# Swarm_Board.net
KiCad netlist of a schematic drawn in EAGLE
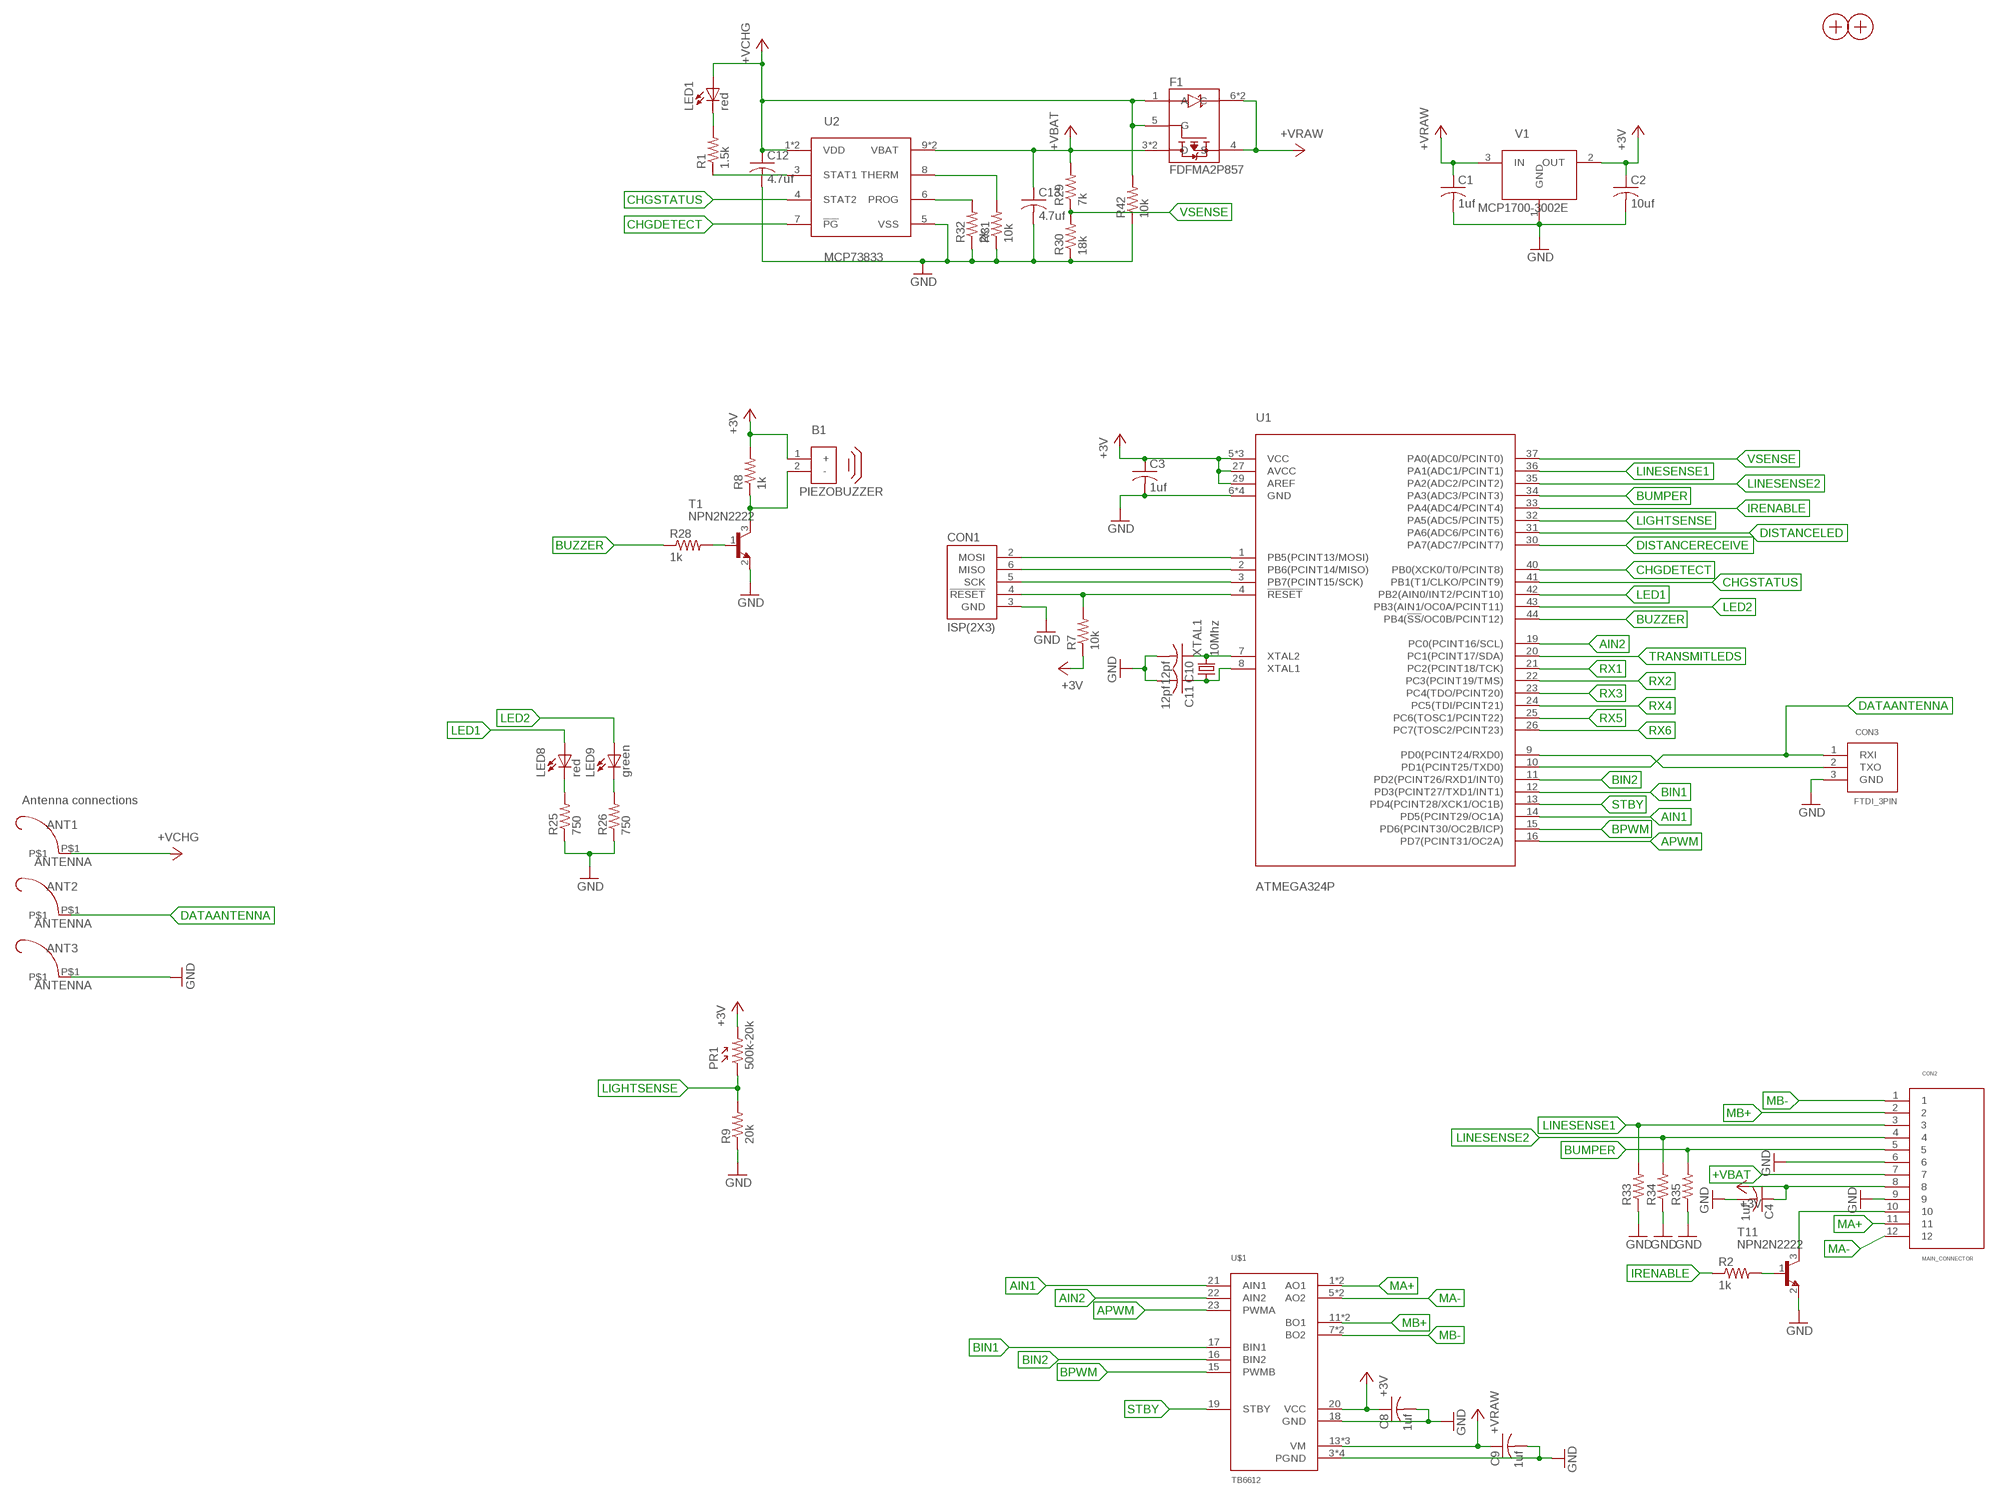
[diagram p0: schematic, sheet 1, part 1 of 2]
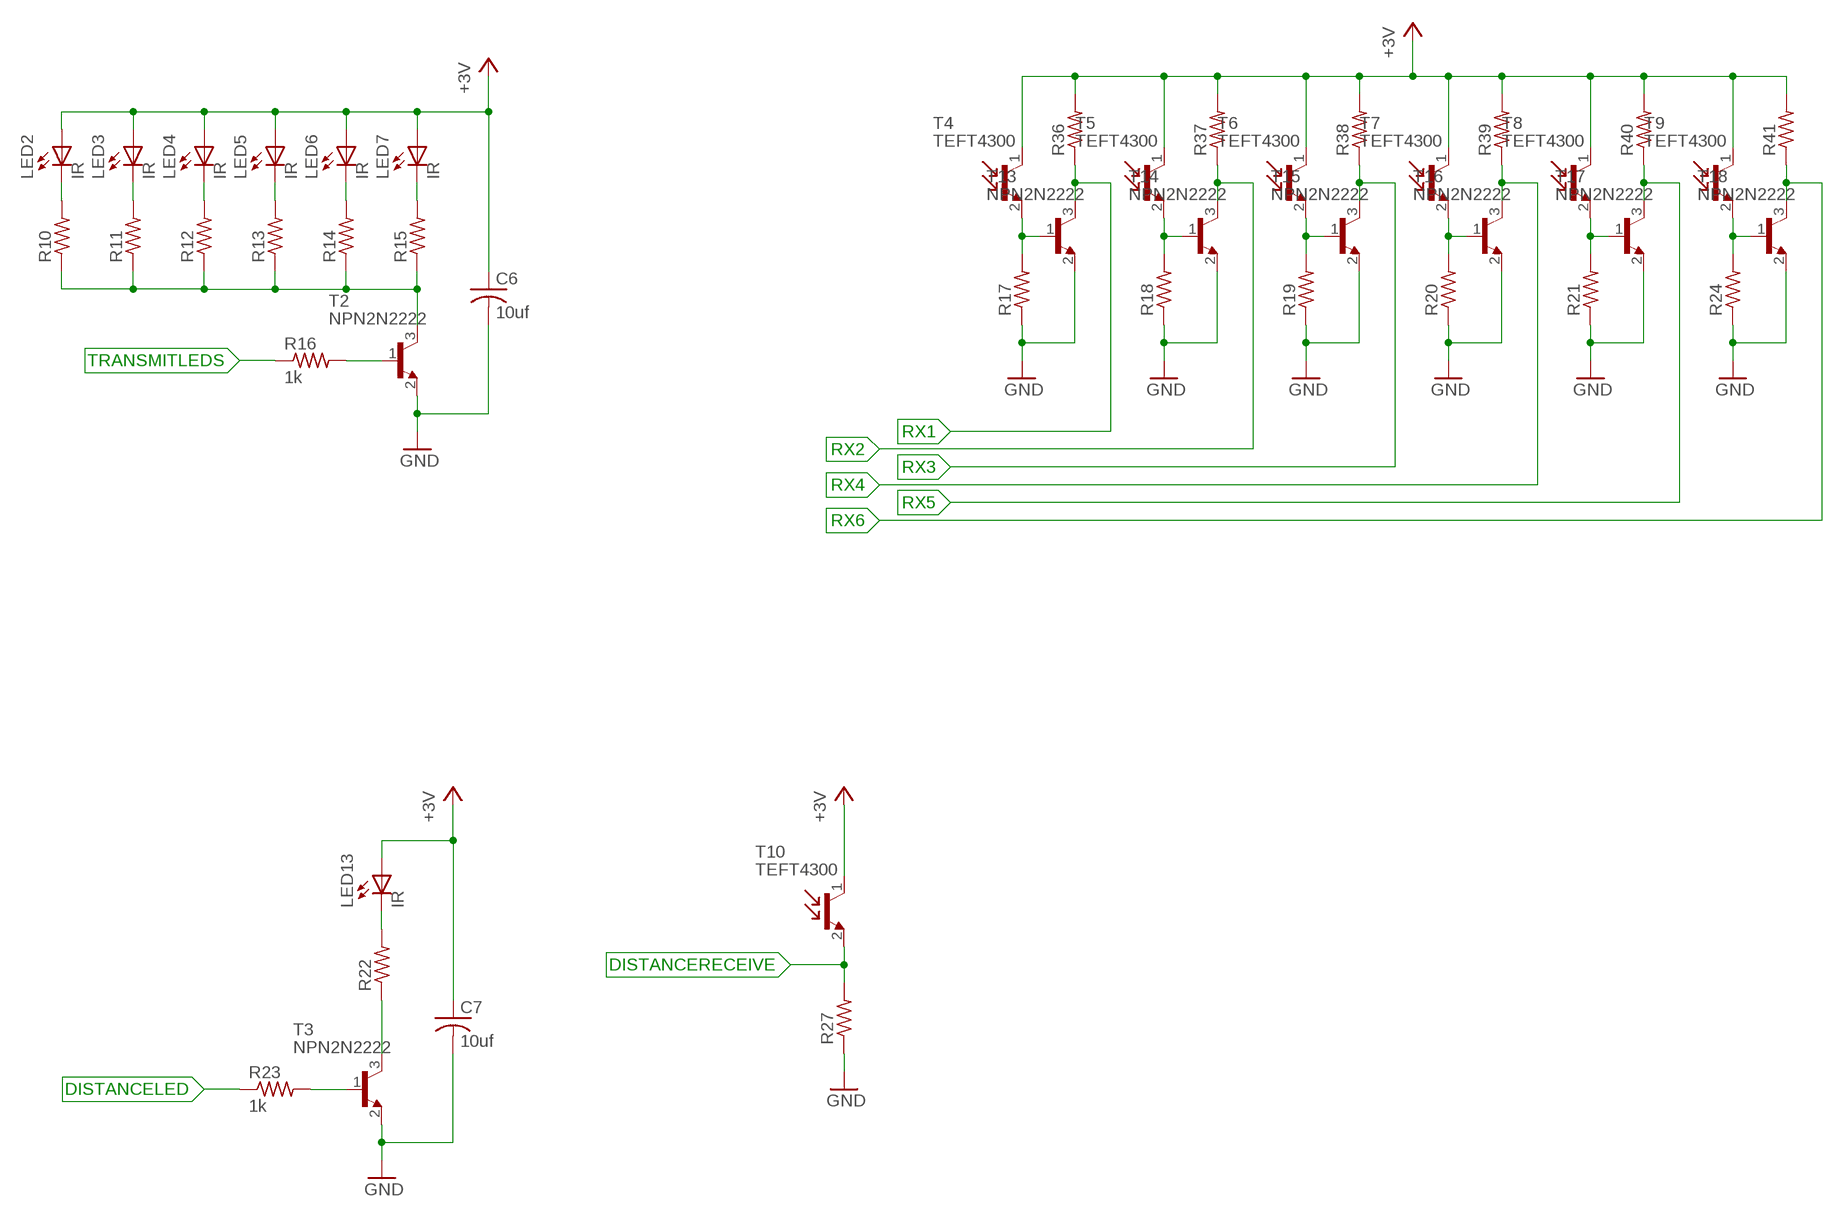
[diagram p1: schematic, sheet 1, part 2 of 2]

(export (version "E")
  (design (tool "Eeschema 10.0.6"))
  (components
    (comp (ref "ANT1")
      (value "ANTENNA")
      (footprint "eagle-import:ANTENNA")
      (libsource (lib "eagle-import") (part "ANTENNA"))
    )
    (comp (ref "ANT2")
      (value "ANTENNA")
      (footprint "eagle-import:ANTENNA")
      (libsource (lib "eagle-import") (part "ANTENNA"))
    )
    (comp (ref "ANT3")
      (value "ANTENNA")
      (footprint "eagle-import:ANTENNA")
      (libsource (lib "eagle-import") (part "ANTENNA"))
    )
    (comp (ref "B1")
      (value "PIEZOBUZZER")
      (footprint "eagle-import:PIEZOBUZZER")
      (libsource (lib "eagle-import") (part "PIEZOBUZZER"))
    )
    (comp (ref "C1")
      (value "1uf")
      (footprint "eagle-import:0603")
      (libsource (lib "eagle-import") (part "CAP0603"))
    )
    (comp (ref "C2")
      (value "10uf")
      (footprint "eagle-import:0805")
      (libsource (lib "eagle-import") (part "CAP0805"))
    )
    (comp (ref "C3")
      (value "1uf")
      (footprint "eagle-import:0603")
      (libsource (lib "eagle-import") (part "CAP0603"))
    )
    (comp (ref "C4")
      (value "1uf")
      (footprint "eagle-import:0603")
      (libsource (lib "eagle-import") (part "CAP0603"))
    )
    (comp (ref "C6")
      (value "10uf")
      (footprint "eagle-import:0805")
      (libsource (lib "eagle-import") (part "CAP0805"))
    )
    (comp (ref "C7")
      (value "10uf")
      (footprint "eagle-import:0805")
      (libsource (lib "eagle-import") (part "CAP0805"))
    )
    (comp (ref "C8")
      (value "1uf")
      (footprint "eagle-import:0603")
      (libsource (lib "eagle-import") (part "CAP0603"))
    )
    (comp (ref "C9")
      (value "1uf")
      (footprint "eagle-import:0603")
      (libsource (lib "eagle-import") (part "CAP0603"))
    )
    (comp (ref "C10")
      (value "12pf")
      (footprint "eagle-import:0603")
      (libsource (lib "eagle-import") (part "CAP0603"))
    )
    (comp (ref "C11")
      (value "12pf")
      (footprint "eagle-import:0603")
      (libsource (lib "eagle-import") (part "CAP0603"))
    )
    (comp (ref "C12")
      (value "4.7uf")
      (footprint "eagle-import:0603")
      (libsource (lib "eagle-import") (part "CAP0603"))
    )
    (comp (ref "C13")
      (value "4.7uf")
      (footprint "eagle-import:0603")
      (libsource (lib "eagle-import") (part "CAP0603"))
    )
    (comp (ref "CON1")
      (value "ISP(2X3)")
      (footprint "eagle-import:PINHEADER(2X3)")
      (libsource (lib "eagle-import") (part "ISP(2X3)"))
    )
    (comp (ref "CON2")
      (value "MAIN_CONNECTOR")
      (footprint "eagle-import:FEMALE_HEADER_2MM_2X6")
      (libsource (lib "eagle-import") (part "MAIN_CONNECTOR"))
    )
    (comp (ref "CON3")
      (value "FTDI_3PIN")
      (footprint "eagle-import:3PINHEADER_.100_")
      (libsource (lib "eagle-import") (part "FTDI_3PIN"))
    )
    (comp (ref "F1")
      (value "FDFMA2P857")
      (footprint "eagle-import:MICROFET2X2MM")
      (libsource (lib "eagle-import") (part "FDFMA2P857"))
    )
    (comp (ref "H1")
      (value "MOUNTINGHOLE")
      (footprint "eagle-import:MOUNTINGHOLE")
      (libsource (lib "eagle-import") (part "MOUNTINGHOLE"))
    )
    (comp (ref "H2")
      (value "MOUNTINGHOLE")
      (footprint "eagle-import:MOUNTINGHOLE")
      (libsource (lib "eagle-import") (part "MOUNTINGHOLE"))
    )
    (comp (ref "LED1")
      (value "red")
      (footprint "eagle-import:LED0603")
      (libsource (lib "eagle-import") (part "LED0603"))
    )
    (comp (ref "LED2")
      (value "IR")
      (footprint "eagle-import:5MM_LED_RA")
      (libsource (lib "eagle-import") (part "LED5MMRA"))
    )
    (comp (ref "LED3")
      (value "IR")
      (footprint "eagle-import:5MM_LED_RA")
      (libsource (lib "eagle-import") (part "LED5MMRA"))
    )
    (comp (ref "LED4")
      (value "IR")
      (footprint "eagle-import:5MM_LED_RA")
      (libsource (lib "eagle-import") (part "LED5MMRA"))
    )
    (comp (ref "LED5")
      (value "IR")
      (footprint "eagle-import:5MM_LED_RA")
      (libsource (lib "eagle-import") (part "LED5MMRA"))
    )
    (comp (ref "LED6")
      (value "IR")
      (footprint "eagle-import:5MM_LED_RA")
      (libsource (lib "eagle-import") (part "LED5MMRA"))
    )
    (comp (ref "LED7")
      (value "IR")
      (footprint "eagle-import:5MM_LED_RA")
      (libsource (lib "eagle-import") (part "LED5MMRA"))
    )
    (comp (ref "LED8")
      (value "red")
      (footprint "eagle-import:LED0603")
      (libsource (lib "eagle-import") (part "LED0603"))
    )
    (comp (ref "LED9")
      (value "green")
      (footprint "eagle-import:LED0603")
      (libsource (lib "eagle-import") (part "LED0603"))
    )
    (comp (ref "LED13")
      (value "IR")
      (footprint "eagle-import:5MM_LED_RA")
      (libsource (lib "eagle-import") (part "LED5MMRA"))
    )
    (comp (ref "PR1")
      (value "500k-20k")
      (footprint "eagle-import:CDSPHOTOCELL")
      (libsource (lib "eagle-import") (part "CDSPHOTORESISTOR"))
    )
    (comp (ref "R1")
      (value "1.5k")
      (footprint "eagle-import:0603")
      (libsource (lib "eagle-import") (part "RES0603"))
    )
    (comp (ref "R2")
      (value "1k")
      (footprint "eagle-import:0603")
      (libsource (lib "eagle-import") (part "RES0603"))
    )
    (comp (ref "R7")
      (value "10k")
      (footprint "eagle-import:0603")
      (libsource (lib "eagle-import") (part "RES0603"))
    )
    (comp (ref "R8")
      (value "1k")
      (footprint "eagle-import:0603")
      (libsource (lib "eagle-import") (part "RES0603"))
    )
    (comp (ref "R9")
      (value "20k")
      (footprint "eagle-import:0603")
      (libsource (lib "eagle-import") (part "RES0603"))
    )
    (comp (ref "R10")
      (value "RES0603")
      (footprint "eagle-import:0603")
      (libsource (lib "eagle-import") (part "RES0603"))
    )
    (comp (ref "R11")
      (value "RES0603")
      (footprint "eagle-import:0603")
      (libsource (lib "eagle-import") (part "RES0603"))
    )
    (comp (ref "R12")
      (value "RES0603")
      (footprint "eagle-import:0603")
      (libsource (lib "eagle-import") (part "RES0603"))
    )
    (comp (ref "R13")
      (value "RES0603")
      (footprint "eagle-import:0603")
      (libsource (lib "eagle-import") (part "RES0603"))
    )
    (comp (ref "R14")
      (value "RES0603")
      (footprint "eagle-import:0603")
      (libsource (lib "eagle-import") (part "RES0603"))
    )
    (comp (ref "R15")
      (value "RES0603")
      (footprint "eagle-import:0603")
      (libsource (lib "eagle-import") (part "RES0603"))
    )
    (comp (ref "R16")
      (value "1k")
      (footprint "eagle-import:0603")
      (libsource (lib "eagle-import") (part "RES0603"))
    )
    (comp (ref "R17")
      (value "RES0603")
      (footprint "eagle-import:0603")
      (libsource (lib "eagle-import") (part "RES0603"))
    )
    (comp (ref "R18")
      (value "RES0603")
      (footprint "eagle-import:0603")
      (libsource (lib "eagle-import") (part "RES0603"))
    )
    (comp (ref "R19")
      (value "RES0603")
      (footprint "eagle-import:0603")
      (libsource (lib "eagle-import") (part "RES0603"))
    )
    (comp (ref "R20")
      (value "RES0603")
      (footprint "eagle-import:0603")
      (libsource (lib "eagle-import") (part "RES0603"))
    )
    (comp (ref "R21")
      (value "RES0603")
      (footprint "eagle-import:0603")
      (libsource (lib "eagle-import") (part "RES0603"))
    )
    (comp (ref "R22")
      (value "RES0603")
      (footprint "eagle-import:0603")
      (libsource (lib "eagle-import") (part "RES0603"))
    )
    (comp (ref "R23")
      (value "1k")
      (footprint "eagle-import:0603")
      (libsource (lib "eagle-import") (part "RES0603"))
    )
    (comp (ref "R24")
      (value "RES0603")
      (footprint "eagle-import:0603")
      (libsource (lib "eagle-import") (part "RES0603"))
    )
    (comp (ref "R25")
      (value "750")
      (footprint "eagle-import:0603")
      (libsource (lib "eagle-import") (part "RES0603"))
    )
    (comp (ref "R26")
      (value "750")
      (footprint "eagle-import:0603")
      (libsource (lib "eagle-import") (part "RES0603"))
    )
    (comp (ref "R27")
      (value "RES0603")
      (footprint "eagle-import:0603")
      (libsource (lib "eagle-import") (part "RES0603"))
    )
    (comp (ref "R28")
      (value "1k")
      (footprint "eagle-import:0603")
      (libsource (lib "eagle-import") (part "RES0603"))
    )
    (comp (ref "R29")
      (value "7k")
      (footprint "eagle-import:0603")
      (libsource (lib "eagle-import") (part "RES0603"))
    )
    (comp (ref "R30")
      (value "18k")
      (footprint "eagle-import:0603")
      (libsource (lib "eagle-import") (part "RES0603"))
    )
    (comp (ref "R31")
      (value "10k")
      (footprint "eagle-import:0603")
      (libsource (lib "eagle-import") (part "RES0603"))
    )
    (comp (ref "R32")
      (value "2k")
      (footprint "eagle-import:0603")
      (libsource (lib "eagle-import") (part "RES0603"))
    )
    (comp (ref "R33")
      (value "RES0603")
      (footprint "eagle-import:0603")
      (libsource (lib "eagle-import") (part "RES0603"))
    )
    (comp (ref "R34")
      (value "RES0603")
      (footprint "eagle-import:0603")
      (libsource (lib "eagle-import") (part "RES0603"))
    )
    (comp (ref "R35")
      (value "RES0603")
      (footprint "eagle-import:0603")
      (libsource (lib "eagle-import") (part "RES0603"))
    )
    (comp (ref "R36")
      (value "RES0603")
      (footprint "eagle-import:0603")
      (libsource (lib "eagle-import") (part "RES0603"))
    )
    (comp (ref "R37")
      (value "RES0603")
      (footprint "eagle-import:0603")
      (libsource (lib "eagle-import") (part "RES0603"))
    )
    (comp (ref "R38")
      (value "RES0603")
      (footprint "eagle-import:0603")
      (libsource (lib "eagle-import") (part "RES0603"))
    )
    (comp (ref "R39")
      (value "RES0603")
      (footprint "eagle-import:0603")
      (libsource (lib "eagle-import") (part "RES0603"))
    )
    (comp (ref "R40")
      (value "RES0603")
      (footprint "eagle-import:0603")
      (libsource (lib "eagle-import") (part "RES0603"))
    )
    (comp (ref "R41")
      (value "RES0603")
      (footprint "eagle-import:0603")
      (libsource (lib "eagle-import") (part "RES0603"))
    )
    (comp (ref "R42")
      (value "10k")
      (footprint "eagle-import:0603")
      (libsource (lib "eagle-import") (part "RES0603"))
    )
    (comp (ref "T1")
      (value "NPN2N2222")
      (footprint "eagle-import:SOT23")
      (libsource (lib "eagle-import") (part "NPN2N2222"))
    )
    (comp (ref "T2")
      (value "NPN2N2222")
      (footprint "eagle-import:SOT23")
      (libsource (lib "eagle-import") (part "NPN2N2222"))
    )
    (comp (ref "T3")
      (value "NPN2N2222")
      (footprint "eagle-import:SOT23")
      (libsource (lib "eagle-import") (part "NPN2N2222"))
    )
    (comp (ref "T4")
      (value "TEFT4300")
      (footprint "eagle-import:3MM_LED_RA")
      (libsource (lib "eagle-import") (part "TEFT4300"))
    )
    (comp (ref "T5")
      (value "TEFT4300")
      (footprint "eagle-import:3MM_LED_RA")
      (libsource (lib "eagle-import") (part "TEFT4300"))
    )
    (comp (ref "T6")
      (value "TEFT4300")
      (footprint "eagle-import:3MM_LED_RA")
      (libsource (lib "eagle-import") (part "TEFT4300"))
    )
    (comp (ref "T7")
      (value "TEFT4300")
      (footprint "eagle-import:3MM_LED_RA")
      (libsource (lib "eagle-import") (part "TEFT4300"))
    )
    (comp (ref "T8")
      (value "TEFT4300")
      (footprint "eagle-import:3MM_LED_RA")
      (libsource (lib "eagle-import") (part "TEFT4300"))
    )
    (comp (ref "T9")
      (value "TEFT4300")
      (footprint "eagle-import:3MM_LED_RA")
      (libsource (lib "eagle-import") (part "TEFT4300"))
    )
    (comp (ref "T10")
      (value "TEFT4300")
      (footprint "eagle-import:3MM_LED_RA")
      (libsource (lib "eagle-import") (part "TEFT4300"))
    )
    (comp (ref "T11")
      (value "NPN2N2222")
      (footprint "eagle-import:SOT23")
      (libsource (lib "eagle-import") (part "NPN2N2222"))
    )
    (comp (ref "T13")
      (value "NPN2N2222")
      (footprint "eagle-import:SOT23")
      (libsource (lib "eagle-import") (part "NPN2N2222"))
    )
    (comp (ref "T14")
      (value "NPN2N2222")
      (footprint "eagle-import:SOT23")
      (libsource (lib "eagle-import") (part "NPN2N2222"))
    )
    (comp (ref "T15")
      (value "NPN2N2222")
      (footprint "eagle-import:SOT23")
      (libsource (lib "eagle-import") (part "NPN2N2222"))
    )
    (comp (ref "T16")
      (value "NPN2N2222")
      (footprint "eagle-import:SOT23")
      (libsource (lib "eagle-import") (part "NPN2N2222"))
    )
    (comp (ref "T17")
      (value "NPN2N2222")
      (footprint "eagle-import:SOT23")
      (libsource (lib "eagle-import") (part "NPN2N2222"))
    )
    (comp (ref "T18")
      (value "NPN2N2222")
      (footprint "eagle-import:SOT23")
      (libsource (lib "eagle-import") (part "NPN2N2222"))
    )
    (comp (ref "U$1")
      (value "TB6612")
      (footprint "eagle-import:24SSOP")
      (libsource (lib "eagle-import") (part "TB6612"))
    )
    (comp (ref "U1")
      (value "ATMEGA324P")
      (footprint "eagle-import:TQFP44")
      (libsource (lib "eagle-import") (part "ATMEGA324P"))
    )
    (comp (ref "U2")
      (value "MCP73833")
      (footprint "eagle-import:MSOP10")
      (libsource (lib "eagle-import") (part "MCP73833"))
    )
    (comp (ref "V1")
      (value "MCP1700-3002E")
      (footprint "eagle-import:(TT_NB)SOT-23(3PAD)")
      (libsource (lib "eagle-import") (part "MCP1700-3002E"))
    )
    (comp (ref "XTAL1")
      (value "10Mhz")
      (footprint "eagle-import:SMDXTAL")
      (libsource (lib "eagle-import") (part "NX5032GA-10.000000MHZ"))
    )
  )
  (nets
    (net (code "1") (name "+3V") (class "Default")
      (node (ref "B1") (pin "1") (pinfunction "+_1") (pintype "bidirectional"))
      (node (ref "C2") (pin "1") (pinfunction "1_1") (pintype "passive"))
      (node (ref "C3") (pin "1") (pinfunction "1_1") (pintype "passive"))
      (node (ref "C4") (pin "1") (pinfunction "1_1") (pintype "passive"))
      (node (ref "C6") (pin "1") (pinfunction "1_1") (pintype "passive"))
      (node (ref "C7") (pin "1") (pinfunction "1_1") (pintype "passive"))
      (node (ref "C8") (pin "1") (pinfunction "1_1") (pintype "passive"))
      (node (ref "CON2") (pin "8") (pinfunction "8_8") (pintype "bidirectional"))
      (node (ref "LED13") (pin "1") (pinfunction "A_1") (pintype "passive"))
      (node (ref "LED2") (pin "1") (pinfunction "A_1") (pintype "passive"))
      (node (ref "LED3") (pin "1") (pinfunction "A_1") (pintype "passive"))
      (node (ref "LED4") (pin "1") (pinfunction "A_1") (pintype "passive"))
      (node (ref "LED5") (pin "1") (pinfunction "A_1") (pintype "passive"))
      (node (ref "LED6") (pin "1") (pinfunction "A_1") (pintype "passive"))
      (node (ref "LED7") (pin "1") (pinfunction "A_1") (pintype "passive"))
      (node (ref "PR1") (pin "2") (pinfunction "2_2") (pintype "passive"))
      (node (ref "R36") (pin "2") (pinfunction "2_2") (pintype "passive"))
      (node (ref "R37") (pin "2") (pinfunction "2_2") (pintype "passive"))
      (node (ref "R38") (pin "2") (pinfunction "2_2") (pintype "passive"))
      (node (ref "R39") (pin "2") (pinfunction "2_2") (pintype "passive"))
      (node (ref "R40") (pin "2") (pinfunction "2_2") (pintype "passive"))
      (node (ref "R41") (pin "2") (pinfunction "2_2") (pintype "passive"))
      (node (ref "R7") (pin "1") (pinfunction "1_1") (pintype "passive"))
      (node (ref "R8") (pin "2") (pinfunction "2_2") (pintype "passive"))
      (node (ref "T10") (pin "1") (pinfunction "C_1") (pintype "passive"))
      (node (ref "T4") (pin "1") (pinfunction "C_1") (pintype "passive"))
      (node (ref "T5") (pin "1") (pinfunction "C_1") (pintype "passive"))
      (node (ref "T6") (pin "1") (pinfunction "C_1") (pintype "passive"))
      (node (ref "T7") (pin "1") (pinfunction "C_1") (pintype "passive"))
      (node (ref "T8") (pin "1") (pinfunction "C_1") (pintype "passive"))
      (node (ref "T9") (pin "1") (pinfunction "C_1") (pintype "passive"))
      (node (ref "U$1") (pin "20") (pinfunction "VCC_20") (pintype "bidirectional"))
      (node (ref "U1") (pin "17") (pinfunction "VCC_17") (pintype "bidirectional"))
      (node (ref "U1") (pin "27") (pinfunction "AVCC_27") (pintype "bidirectional"))
      (node (ref "U1") (pin "29") (pinfunction "AREF_29") (pintype "bidirectional"))
      (node (ref "U1") (pin "38") (pinfunction "VCC_38") (pintype "bidirectional"))
      (node (ref "U1") (pin "5") (pinfunction "VCC_5") (pintype "bidirectional"))
      (node (ref "V1") (pin "2") (pinfunction "OUT_2") (pintype "bidirectional"))
    )
    (net (code "2") (name "+VBAT") (class "Default")
      (node (ref "C13") (pin "1") (pinfunction "1_1") (pintype "passive"))
      (node (ref "CON2") (pin "7") (pinfunction "7_7") (pintype "bidirectional"))
      (node (ref "F1") (pin "3") (pinfunction "D_3") (pintype "bidirectional"))
      (node (ref "F1") (pin "8") (pinfunction "D_8") (pintype "bidirectional"))
      (node (ref "R29") (pin "2") (pinfunction "2_2") (pintype "passive"))
      (node (ref "U2") (pin "10") (pinfunction "VBAT_10") (pintype "bidirectional"))
      (node (ref "U2") (pin "9") (pinfunction "VBAT_9") (pintype "bidirectional"))
    )
    (net (code "3") (name "+VCHG") (class "Default")
      (node (ref "ANT1") (pin "P$1") (pinfunction "P$1_P$1") (pintype "bidirectional"))
      (node (ref "C12") (pin "1") (pinfunction "1_1") (pintype "passive"))
      (node (ref "F1") (pin "1") (pinfunction "A_1") (pintype "bidirectional"))
      (node (ref "F1") (pin "5") (pinfunction "G_5") (pintype "bidirectional"))
      (node (ref "LED1") (pin "2") (pinfunction "A_2") (pintype "passive"))
      (node (ref "R42") (pin "2") (pinfunction "2_2") (pintype "passive"))
      (node (ref "U2") (pin "1") (pinfunction "VDD_1") (pintype "bidirectional"))
      (node (ref "U2") (pin "2") (pinfunction "VDD_2") (pintype "bidirectional"))
    )
    (net (code "4") (name "+VRAW") (class "Default")
      (node (ref "C1") (pin "1") (pinfunction "1_1") (pintype "passive"))
      (node (ref "C9") (pin "1") (pinfunction "1_1") (pintype "passive"))
      (node (ref "F1") (pin "4") (pinfunction "S_4") (pintype "bidirectional"))
      (node (ref "F1") (pin "6") (pinfunction "C_6") (pintype "bidirectional"))
      (node (ref "F1") (pin "7") (pinfunction "C_7") (pintype "bidirectional"))
      (node (ref "U$1") (pin "13") (pinfunction "VM_13") (pintype "bidirectional"))
      (node (ref "U$1") (pin "14") (pinfunction "VM_14") (pintype "bidirectional"))
      (node (ref "U$1") (pin "24") (pinfunction "VM_24") (pintype "bidirectional"))
      (node (ref "V1") (pin "3") (pinfunction "IN_3") (pintype "bidirectional"))
    )
    (net (code "5") (name "AIN1") (class "Default")
      (node (ref "U$1") (pin "21") (pinfunction "AIN1_21") (pintype "bidirectional"))
      (node (ref "U1") (pin "14") (pinfunction "PD5(PCINT29/OC1A)_14") (pintype "bidirectional"))
    )
    (net (code "6") (name "AIN2") (class "Default")
      (node (ref "U$1") (pin "22") (pinfunction "AIN2_22") (pintype "bidirectional"))
      (node (ref "U1") (pin "19") (pinfunction "PC0(PCINT16/SCL)_19") (pintype "bidirectional"))
    )
    (net (code "7") (name "APWM") (class "Default")
      (node (ref "U$1") (pin "23") (pinfunction "PWMA_23") (pintype "bidirectional"))
      (node (ref "U1") (pin "16") (pinfunction "PD7(PCINT31/OC2A)_16") (pintype "bidirectional"))
    )
    (net (code "8") (name "BIN1") (class "Default")
      (node (ref "U$1") (pin "17") (pinfunction "BIN1_17") (pintype "bidirectional"))
      (node (ref "U1") (pin "12") (pinfunction "PD3(PCINT27/TXD1/INT1)_12") (pintype "bidirectional"))
    )
    (net (code "9") (name "BIN2") (class "Default")
      (node (ref "U$1") (pin "16") (pinfunction "BIN2_16") (pintype "bidirectional"))
      (node (ref "U1") (pin "11") (pinfunction "PD2(PCINT26/RXD1/INT0)_11") (pintype "bidirectional"))
    )
    (net (code "10") (name "BPWM") (class "Default")
      (node (ref "U$1") (pin "15") (pinfunction "PWMB_15") (pintype "bidirectional"))
      (node (ref "U1") (pin "15") (pinfunction "PD6(PCINT30/OC2B/ICP)_15") (pintype "bidirectional"))
    )
    (net (code "11") (name "BUMPER") (class "Default")
      (node (ref "CON2") (pin "5") (pinfunction "5_5") (pintype "bidirectional"))
      (node (ref "R35") (pin "2") (pinfunction "2_2") (pintype "passive"))
      (node (ref "U1") (pin "34") (pinfunction "PA3(ADC3/PCINT3)_34") (pintype "bidirectional"))
    )
    (net (code "12") (name "BUZZER") (class "Default")
      (node (ref "R28") (pin "1") (pinfunction "1_1") (pintype "passive"))
      (node (ref "U1") (pin "44") (pinfunction "PB4(~{SS}/OC0B/PCINT12)_44") (pintype "bidirectional"))
    )
    (net (code "13") (name "CHGDETECT") (class "Default")
      (node (ref "U1") (pin "40") (pinfunction "PB0(XCK0/T0/PCINT8)_40") (pintype "bidirectional"))
      (node (ref "U2") (pin "7") (pinfunction "~{PG}_7") (pintype "bidirectional"))
    )
    (net (code "14") (name "CHGSTATUS") (class "Default")
      (node (ref "U1") (pin "41") (pinfunction "PB1(T1/CLKO/PCINT9)_41") (pintype "bidirectional"))
      (node (ref "U2") (pin "4") (pinfunction "STAT2_4") (pintype "bidirectional"))
    )
    (net (code "15") (name "DATAANTENNA") (class "Default")
      (node (ref "ANT2") (pin "P$1") (pinfunction "P$1_P$1") (pintype "bidirectional"))
      (node (ref "CON3") (pin "1") (pinfunction "RXI_1") (pintype "bidirectional"))
      (node (ref "U1") (pin "10") (pinfunction "PD1(PCINT25/TXD0)_10") (pintype "bidirectional"))
    )
    (net (code "16") (name "DISTANCELED") (class "Default")
      (node (ref "R23") (pin "1") (pinfunction "1_1") (pintype "passive"))
      (node (ref "U1") (pin "31") (pinfunction "PA6(ADC6/PCINT6)_31") (pintype "bidirectional"))
    )
    (net (code "17") (name "DISTANCERECEIVE") (class "Default")
      (node (ref "R27") (pin "2") (pinfunction "2_2") (pintype "passive"))
      (node (ref "T10") (pin "2") (pinfunction "E_2") (pintype "passive"))
      (node (ref "U1") (pin "30") (pinfunction "PA7(ADC7/PCINT7)_30") (pintype "bidirectional"))
    )
    (net (code "18") (name "GND") (class "Default")
      (node (ref "ANT3") (pin "P$1") (pinfunction "P$1_P$1") (pintype "bidirectional"))
      (node (ref "C1") (pin "2") (pinfunction "2_2") (pintype "passive"))
      (node (ref "C10") (pin "2") (pinfunction "2_2") (pintype "passive"))
      (node (ref "C11") (pin "2") (pinfunction "2_2") (pintype "passive"))
      (node (ref "C12") (pin "2") (pinfunction "2_2") (pintype "passive"))
      (node (ref "C13") (pin "2") (pinfunction "2_2") (pintype "passive"))
      (node (ref "C2") (pin "2") (pinfunction "2_2") (pintype "passive"))
      (node (ref "C3") (pin "2") (pinfunction "2_2") (pintype "passive"))
      (node (ref "C4") (pin "2") (pinfunction "2_2") (pintype "passive"))
      (node (ref "C6") (pin "2") (pinfunction "2_2") (pintype "passive"))
      (node (ref "C7") (pin "2") (pinfunction "2_2") (pintype "passive"))
      (node (ref "C8") (pin "2") (pinfunction "2_2") (pintype "passive"))
      (node (ref "C9") (pin "2") (pinfunction "2_2") (pintype "passive"))
      (node (ref "CON1") (pin "3") (pinfunction "GND_3") (pintype "bidirectional"))
      (node (ref "CON2") (pin "6") (pinfunction "6_6") (pintype "bidirectional"))
      (node (ref "CON2") (pin "9") (pinfunction "9_9") (pintype "bidirectional"))
      (node (ref "CON3") (pin "3") (pinfunction "GND_3") (pintype "bidirectional"))
      (node (ref "R17") (pin "1") (pinfunction "1_1") (pintype "passive"))
      (node (ref "R18") (pin "1") (pinfunction "1_1") (pintype "passive"))
      (node (ref "R19") (pin "1") (pinfunction "1_1") (pintype "passive"))
      (node (ref "R20") (pin "1") (pinfunction "1_1") (pintype "passive"))
      (node (ref "R21") (pin "1") (pinfunction "1_1") (pintype "passive"))
      (node (ref "R24") (pin "1") (pinfunction "1_1") (pintype "passive"))
      (node (ref "R25") (pin "1") (pinfunction "1_1") (pintype "passive"))
      (node (ref "R26") (pin "1") (pinfunction "1_1") (pintype "passive"))
      (node (ref "R27") (pin "1") (pinfunction "1_1") (pintype "passive"))
      (node (ref "R30") (pin "1") (pinfunction "1_1") (pintype "passive"))
      (node (ref "R31") (pin "1") (pinfunction "1_1") (pintype "passive"))
      (node (ref "R32") (pin "1") (pinfunction "1_1") (pintype "passive"))
      (node (ref "R33") (pin "1") (pinfunction "1_1") (pintype "passive"))
      (node (ref "R34") (pin "1") (pinfunction "1_1") (pintype "passive"))
      (node (ref "R35") (pin "1") (pinfunction "1_1") (pintype "passive"))
      (node (ref "R42") (pin "1") (pinfunction "1_1") (pintype "passive"))
      (node (ref "R9") (pin "1") (pinfunction "1_1") (pintype "passive"))
      (node (ref "T1") (pin "2") (pinfunction "E_2") (pintype "passive"))
      (node (ref "T11") (pin "2") (pinfunction "E_2") (pintype "passive"))
      (node (ref "T13") (pin "2") (pinfunction "E_2") (pintype "passive"))
      (node (ref "T14") (pin "2") (pinfunction "E_2") (pintype "passive"))
      (node (ref "T15") (pin "2") (pinfunction "E_2") (pintype "passive"))
      (node (ref "T16") (pin "2") (pinfunction "E_2") (pintype "passive"))
      (node (ref "T17") (pin "2") (pinfunction "E_2") (pintype "passive"))
      (node (ref "T18") (pin "2") (pinfunction "E_2") (pintype "passive"))
      (node (ref "T2") (pin "2") (pinfunction "E_2") (pintype "passive"))
      (node (ref "T3") (pin "2") (pinfunction "E_2") (pintype "passive"))
      (node (ref "U$1") (pin "10") (pinfunction "PGND_10") (pintype "bidirectional"))
      (node (ref "U$1") (pin "18") (pinfunction "GND_18") (pintype "bidirectional"))
      (node (ref "U$1") (pin "3") (pinfunction "PGND_3") (pintype "bidirectional"))
      (node (ref "U$1") (pin "4") (pinfunction "PGND_4") (pintype "bidirectional"))
      (node (ref "U$1") (pin "9") (pinfunction "PGND_9") (pintype "bidirectional"))
      (node (ref "U1") (pin "18") (pinfunction "GND_18") (pintype "bidirectional"))
      (node (ref "U1") (pin "28") (pinfunction "GND_28") (pintype "bidirectional"))
      (node (ref "U1") (pin "39") (pinfunction "GND_39") (pintype "bidirectional"))
      (node (ref "U1") (pin "6") (pinfunction "GND_6") (pintype "bidirectional"))
      (node (ref "U2") (pin "5") (pinfunction "VSS_5") (pintype "bidirectional"))
      (node (ref "V1") (pin "1") (pinfunction "GND_1") (pintype "bidirectional"))
    )
    (net (code "19") (name "IRENABLE") (class "Default")
      (node (ref "R2") (pin "1") (pinfunction "1_1") (pintype "passive"))
      (node (ref "U1") (pin "33") (pinfunction "PA4(ADC4/PCINT4)_33") (pintype "bidirectional"))
    )
    (net (code "20") (name "LED1") (class "Default")
      (node (ref "LED8") (pin "2") (pinfunction "A_2") (pintype "passive"))
      (node (ref "U1") (pin "42") (pinfunction "PB2(AIN0/INT2/PCINT10)_42") (pintype "bidirectional"))
    )
    (net (code "21") (name "LED2") (class "Default")
      (node (ref "LED9") (pin "2") (pinfunction "A_2") (pintype "passive"))
      (node (ref "U1") (pin "43") (pinfunction "PB3(AIN1/OC0A/PCINT11)_43") (pintype "bidirectional"))
    )
    (net (code "22") (name "LIGHTSENSE") (class "Default")
      (node (ref "PR1") (pin "1") (pinfunction "1_1") (pintype "passive"))
      (node (ref "R9") (pin "2") (pinfunction "2_2") (pintype "passive"))
      (node (ref "U1") (pin "32") (pinfunction "PA5(ADC5/PCINT5)_32") (pintype "bidirectional"))
    )
    (net (code "23") (name "LINESENSE1") (class "Default")
      (node (ref "CON2") (pin "3") (pinfunction "3_3") (pintype "bidirectional"))
      (node (ref "R33") (pin "2") (pinfunction "2_2") (pintype "passive"))
      (node (ref "U1") (pin "36") (pinfunction "PA1(ADC1/PCINT1)_36") (pintype "bidirectional"))
    )
    (net (code "24") (name "LINESENSE2") (class "Default")
      (node (ref "CON2") (pin "4") (pinfunction "4_4") (pintype "bidirectional"))
      (node (ref "R34") (pin "2") (pinfunction "2_2") (pintype "passive"))
      (node (ref "U1") (pin "35") (pinfunction "PA2(ADC2/PCINT2)_35") (pintype "bidirectional"))
    )
    (net (code "25") (name "MA+") (class "Default")
      (node (ref "CON2") (pin "11") (pinfunction "11_11") (pintype "bidirectional"))
      (node (ref "U$1") (pin "1") (pinfunction "AO1_1") (pintype "bidirectional"))
      (node (ref "U$1") (pin "2") (pinfunction "AO1_2") (pintype "bidirectional"))
    )
    (net (code "26") (name "MA-") (class "Default")
      (node (ref "CON2") (pin "12") (pinfunction "12_12") (pintype "bidirectional"))
      (node (ref "U$1") (pin "5") (pinfunction "AO2_5") (pintype "bidirectional"))
      (node (ref "U$1") (pin "6") (pinfunction "AO2_6") (pintype "bidirectional"))
    )
    (net (code "27") (name "MB+") (class "Default")
      (node (ref "CON2") (pin "2") (pinfunction "2_2") (pintype "bidirectional"))
      (node (ref "U$1") (pin "11") (pinfunction "BO1_11") (pintype "bidirectional"))
      (node (ref "U$1") (pin "12") (pinfunction "BO1_12") (pintype "bidirectional"))
    )
    (net (code "28") (name "MB-") (class "Default")
      (node (ref "CON2") (pin "1") (pinfunction "1_1") (pintype "bidirectional"))
      (node (ref "U$1") (pin "7") (pinfunction "BO2_7") (pintype "bidirectional"))
      (node (ref "U$1") (pin "8") (pinfunction "BO2_8") (pintype "bidirectional"))
    )
    (net (code "29") (name "Net-(B1--)") (class "Default")
      (node (ref "B1") (pin "2") (pinfunction "-_2") (pintype "bidirectional"))
      (node (ref "R8") (pin "1") (pinfunction "1_1") (pintype "passive"))
      (node (ref "T1") (pin "3") (pinfunction "C_3") (pintype "passive"))
    )
    (net (code "30") (name "Net-(CON1-MISO)") (class "Default")
      (node (ref "CON1") (pin "6") (pinfunction "MISO_6") (pintype "bidirectional"))
      (node (ref "U1") (pin "2") (pinfunction "PB6(PCINT14/MISO)_2") (pintype "bidirectional"))
    )
    (net (code "31") (name "Net-(CON1-MOSI)") (class "Default")
      (node (ref "CON1") (pin "2") (pinfunction "MOSI_2") (pintype "bidirectional"))
      (node (ref "U1") (pin "1") (pinfunction "PB5(PCINT13/MOSI)_1") (pintype "bidirectional"))
    )
    (net (code "32") (name "Net-(CON1-SCK)") (class "Default")
      (node (ref "CON1") (pin "5") (pinfunction "SCK_5") (pintype "bidirectional"))
      (node (ref "U1") (pin "3") (pinfunction "PB7(PCINT15/SCK)_3") (pintype "bidirectional"))
    )
    (net (code "33") (name "Net-(CON1-~{RESET})") (class "Default")
      (node (ref "CON1") (pin "4") (pinfunction "~{RESET}_4") (pintype "bidirectional"))
      (node (ref "R7") (pin "2") (pinfunction "2_2") (pintype "passive"))
      (node (ref "U1") (pin "4") (pinfunction "~{RESET}_4") (pintype "bidirectional"))
    )
    (net (code "34") (name "Net-(CON3-TXO)") (class "Default")
      (node (ref "CON3") (pin "2") (pinfunction "TXO_2") (pintype "bidirectional"))
      (node (ref "U1") (pin "9") (pinfunction "PD0(PCINT24/RXD0)_9") (pintype "bidirectional"))
    )
    (net (code "35") (name "Net-(LED1-C)") (class "Default")
      (node (ref "LED1") (pin "1") (pinfunction "C_1") (pintype "passive"))
      (node (ref "R1") (pin "2") (pinfunction "2_2") (pintype "passive"))
    )
    (net (code "36") (name "Net-(LED2-C)") (class "Default")
      (node (ref "LED2") (pin "2") (pinfunction "C_2") (pintype "passive"))
      (node (ref "R10") (pin "2") (pinfunction "2_2") (pintype "passive"))
    )
    (net (code "37") (name "Net-(LED3-C)") (class "Default")
      (node (ref "LED3") (pin "2") (pinfunction "C_2") (pintype "passive"))
      (node (ref "R11") (pin "2") (pinfunction "2_2") (pintype "passive"))
    )
    (net (code "38") (name "Net-(LED4-C)") (class "Default")
      (node (ref "LED4") (pin "2") (pinfunction "C_2") (pintype "passive"))
      (node (ref "R12") (pin "2") (pinfunction "2_2") (pintype "passive"))
    )
    (net (code "39") (name "Net-(LED5-C)") (class "Default")
      (node (ref "LED5") (pin "2") (pinfunction "C_2") (pintype "passive"))
      (node (ref "R13") (pin "2") (pinfunction "2_2") (pintype "passive"))
    )
    (net (code "40") (name "Net-(LED6-C)") (class "Default")
      (node (ref "LED6") (pin "2") (pinfunction "C_2") (pintype "passive"))
      (node (ref "R14") (pin "2") (pinfunction "2_2") (pintype "passive"))
    )
    (net (code "41") (name "Net-(LED7-C)") (class "Default")
      (node (ref "LED7") (pin "2") (pinfunction "C_2") (pintype "passive"))
      (node (ref "R15") (pin "2") (pinfunction "2_2") (pintype "passive"))
    )
    (net (code "42") (name "Net-(LED8-C)") (class "Default")
      (node (ref "LED8") (pin "1") (pinfunction "C_1") (pintype "passive"))
      (node (ref "R25") (pin "2") (pinfunction "2_2") (pintype "passive"))
    )
    (net (code "43") (name "Net-(LED9-C)") (class "Default")
      (node (ref "LED9") (pin "1") (pinfunction "C_1") (pintype "passive"))
      (node (ref "R26") (pin "2") (pinfunction "2_2") (pintype "passive"))
    )
    (net (code "44") (name "Net-(LED13-C)") (class "Default")
      (node (ref "LED13") (pin "2") (pinfunction "C_2") (pintype "passive"))
      (node (ref "R22") (pin "2") (pinfunction "2_2") (pintype "passive"))
    )
    (net (code "45") (name "Net-(T1-B)") (class "Default")
      (node (ref "R28") (pin "2") (pinfunction "2_2") (pintype "passive"))
      (node (ref "T1") (pin "1") (pinfunction "B_1") (pintype "passive"))
    )
    (net (code "46") (name "Net-(T2-B)") (class "Default")
      (node (ref "R16") (pin "2") (pinfunction "2_2") (pintype "passive"))
      (node (ref "T2") (pin "1") (pinfunction "B_1") (pintype "passive"))
    )
    (net (code "47") (name "Net-(T2-C)") (class "Default")
      (node (ref "R10") (pin "1") (pinfunction "1_1") (pintype "passive"))
      (node (ref "R11") (pin "1") (pinfunction "1_1") (pintype "passive"))
      (node (ref "R12") (pin "1") (pinfunction "1_1") (pintype "passive"))
      (node (ref "R13") (pin "1") (pinfunction "1_1") (pintype "passive"))
      (node (ref "R14") (pin "1") (pinfunction "1_1") (pintype "passive"))
      (node (ref "R15") (pin "1") (pinfunction "1_1") (pintype "passive"))
      (node (ref "T2") (pin "3") (pinfunction "C_3") (pintype "passive"))
    )
    (net (code "48") (name "Net-(T3-B)") (class "Default")
      (node (ref "R23") (pin "2") (pinfunction "2_2") (pintype "passive"))
      (node (ref "T3") (pin "1") (pinfunction "B_1") (pintype "passive"))
    )
    (net (code "49") (name "Net-(T3-C)") (class "Default")
      (node (ref "R22") (pin "1") (pinfunction "1_1") (pintype "passive"))
      (node (ref "T3") (pin "3") (pinfunction "C_3") (pintype "passive"))
    )
    (net (code "50") (name "Net-(T11-B)") (class "Default")
      (node (ref "R2") (pin "2") (pinfunction "2_2") (pintype "passive"))
      (node (ref "T11") (pin "1") (pinfunction "B_1") (pintype "passive"))
    )
    (net (code "51") (name "Net-(T11-C)") (class "Default")
      (node (ref "CON2") (pin "10") (pinfunction "10_10") (pintype "bidirectional"))
      (node (ref "T11") (pin "3") (pinfunction "C_3") (pintype "passive"))
    )
    (net (code "52") (name "Net-(T13-B)") (class "Default")
      (node (ref "R17") (pin "2") (pinfunction "2_2") (pintype "passive"))
      (node (ref "T13") (pin "1") (pinfunction "B_1") (pintype "passive"))
      (node (ref "T4") (pin "2") (pinfunction "E_2") (pintype "passive"))
    )
    (net (code "53") (name "Net-(T14-B)") (class "Default")
      (node (ref "R18") (pin "2") (pinfunction "2_2") (pintype "passive"))
      (node (ref "T14") (pin "1") (pinfunction "B_1") (pintype "passive"))
      (node (ref "T5") (pin "2") (pinfunction "E_2") (pintype "passive"))
    )
    (net (code "54") (name "Net-(T15-B)") (class "Default")
      (node (ref "R19") (pin "2") (pinfunction "2_2") (pintype "passive"))
      (node (ref "T15") (pin "1") (pinfunction "B_1") (pintype "passive"))
      (node (ref "T6") (pin "2") (pinfunction "E_2") (pintype "passive"))
    )
    (net (code "55") (name "Net-(T16-B)") (class "Default")
      (node (ref "R20") (pin "2") (pinfunction "2_2") (pintype "passive"))
      (node (ref "T16") (pin "1") (pinfunction "B_1") (pintype "passive"))
      (node (ref "T7") (pin "2") (pinfunction "E_2") (pintype "passive"))
    )
    (net (code "56") (name "Net-(T17-B)") (class "Default")
      (node (ref "R21") (pin "2") (pinfunction "2_2") (pintype "passive"))
      (node (ref "T17") (pin "1") (pinfunction "B_1") (pintype "passive"))
      (node (ref "T8") (pin "2") (pinfunction "E_2") (pintype "passive"))
    )
    (net (code "57") (name "Net-(T18-B)") (class "Default")
      (node (ref "R24") (pin "2") (pinfunction "2_2") (pintype "passive"))
      (node (ref "T18") (pin "1") (pinfunction "B_1") (pintype "passive"))
      (node (ref "T9") (pin "2") (pinfunction "E_2") (pintype "passive"))
    )
    (net (code "58") (name "Net-(U1-XTAL1)") (class "Default")
      (node (ref "C11") (pin "1") (pinfunction "1_1") (pintype "passive"))
      (node (ref "U1") (pin "8") (pinfunction "XTAL1_8") (pintype "bidirectional"))
      (node (ref "XTAL1") (pin "1") (pinfunction "1_1") (pintype "passive"))
    )
    (net (code "59") (name "Net-(U1-XTAL2)") (class "Default")
      (node (ref "C10") (pin "1") (pinfunction "1_1") (pintype "passive"))
      (node (ref "U1") (pin "7") (pinfunction "XTAL2_7") (pintype "bidirectional"))
      (node (ref "XTAL1") (pin "2") (pinfunction "2_2") (pintype "passive"))
    )
    (net (code "60") (name "Net-(U2-PROG)") (class "Default")
      (node (ref "R32") (pin "2") (pinfunction "2_2") (pintype "passive"))
      (node (ref "U2") (pin "6") (pinfunction "PROG_6") (pintype "bidirectional"))
    )
    (net (code "61") (name "Net-(U2-STAT1)") (class "Default")
      (node (ref "R1") (pin "1") (pinfunction "1_1") (pintype "passive"))
      (node (ref "U2") (pin "3") (pinfunction "STAT1_3") (pintype "bidirectional"))
    )
    (net (code "62") (name "Net-(U2-THERM)") (class "Default")
      (node (ref "R31") (pin "2") (pinfunction "2_2") (pintype "passive"))
      (node (ref "U2") (pin "8") (pinfunction "THERM_8") (pintype "bidirectional"))
    )
    (net (code "63") (name "RX1") (class "Default")
      (node (ref "R36") (pin "1") (pinfunction "1_1") (pintype "passive"))
      (node (ref "T13") (pin "3") (pinfunction "C_3") (pintype "passive"))
      (node (ref "U1") (pin "21") (pinfunction "PC2(PCINT18/TCK)_21") (pintype "bidirectional"))
    )
    (net (code "64") (name "RX2") (class "Default")
      (node (ref "R37") (pin "1") (pinfunction "1_1") (pintype "passive"))
      (node (ref "T14") (pin "3") (pinfunction "C_3") (pintype "passive"))
      (node (ref "U1") (pin "22") (pinfunction "PC3(PCINT19/TMS)_22") (pintype "bidirectional"))
    )
    (net (code "65") (name "RX3") (class "Default")
      (node (ref "R38") (pin "1") (pinfunction "1_1") (pintype "passive"))
      (node (ref "T15") (pin "3") (pinfunction "C_3") (pintype "passive"))
      (node (ref "U1") (pin "23") (pinfunction "PC4(TDO/PCINT20)_23") (pintype "bidirectional"))
    )
    (net (code "66") (name "RX4") (class "Default")
      (node (ref "R39") (pin "1") (pinfunction "1_1") (pintype "passive"))
      (node (ref "T16") (pin "3") (pinfunction "C_3") (pintype "passive"))
      (node (ref "U1") (pin "24") (pinfunction "PC5(TDI/PCINT21)_24") (pintype "bidirectional"))
    )
    (net (code "67") (name "RX5") (class "Default")
      (node (ref "R40") (pin "1") (pinfunction "1_1") (pintype "passive"))
      (node (ref "T17") (pin "3") (pinfunction "C_3") (pintype "passive"))
      (node (ref "U1") (pin "25") (pinfunction "PC6(TOSC1/PCINT22)_25") (pintype "bidirectional"))
    )
    (net (code "68") (name "RX6") (class "Default")
      (node (ref "R41") (pin "1") (pinfunction "1_1") (pintype "passive"))
      (node (ref "T18") (pin "3") (pinfunction "C_3") (pintype "passive"))
      (node (ref "U1") (pin "26") (pinfunction "PC7(TOSC2/PCINT23)_26") (pintype "bidirectional"))
    )
    (net (code "69") (name "STBY") (class "Default")
      (node (ref "U$1") (pin "19") (pinfunction "STBY_19") (pintype "bidirectional"))
      (node (ref "U1") (pin "13") (pinfunction "PD4(PCINT28/XCK1/OC1B)_13") (pintype "bidirectional"))
    )
    (net (code "70") (name "TRANSMITLEDS") (class "Default")
      (node (ref "R16") (pin "1") (pinfunction "1_1") (pintype "passive"))
      (node (ref "U1") (pin "20") (pinfunction "PC1(PCINT17/SDA)_20") (pintype "bidirectional"))
    )
    (net (code "71") (name "VSENSE") (class "Default")
      (node (ref "R29") (pin "1") (pinfunction "1_1") (pintype "passive"))
      (node (ref "R30") (pin "2") (pinfunction "2_2") (pintype "passive"))
      (node (ref "U1") (pin "37") (pinfunction "PA0(ADC0/PCINT0)_37") (pintype "bidirectional"))
    )
  )
)
